# HM2102NLT_Transformer_Breakout_Board.net
KiCad netlist of a schematic drawn in EAGLE
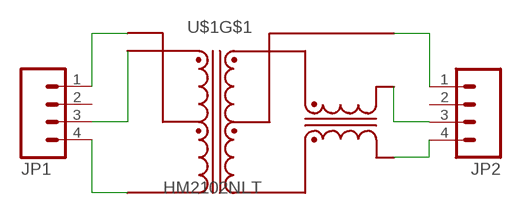
[diagram p0: schematic, sheet 1]

(export (version "E")
  (design (tool "Eeschema 10.0.6"))
  (components
    (comp (ref "JP1")
      (value "M04")
      (footprint "eagle-import:1X04")
      (libsource (lib "eagle-import") (part "M04"))
    )
    (comp (ref "JP2")
      (value "M04")
      (footprint "eagle-import:1X04")
      (libsource (lib "eagle-import") (part "M04"))
    )
    (comp (ref "U$1")
      (value "HM2102NLT")
      (footprint "eagle-import:HM2102NLT")
      (libsource (lib "eagle-import") (part "HM2102NLT"))
    )
  )
  (nets
    (net (code "1") (name "Net-(U$1A-MCT)") (class "Default")
      (node (ref "JP1") (pin "1") (pinfunction "1_1") (pintype "passive"))
      (node (ref "U$1") (pin "P$2") (pinfunction "MCT_P$2") (pintype "passive"))
    )
    (net (code "2") (name "Net-(U$1A-MX+)") (class "Default")
      (node (ref "JP1") (pin "3") (pinfunction "3_3") (pintype "passive"))
      (node (ref "U$1") (pin "P$1") (pinfunction "MX+_P$1") (pintype "passive"))
    )
    (net (code "3") (name "Net-(U$1A-MX-)") (class "Default")
      (node (ref "JP1") (pin "4") (pinfunction "4_4") (pintype "passive"))
      (node (ref "U$1") (pin "P$3") (pinfunction "MX-_P$3") (pintype "passive"))
    )
    (net (code "4") (name "Net-(U$1A-TCT)") (class "Default")
      (node (ref "JP2") (pin "1") (pinfunction "1_1") (pintype "passive"))
      (node (ref "U$1") (pin "P$11") (pinfunction "TCT_P$11") (pintype "passive"))
    )
    (net (code "5") (name "Net-(U$1A-TD+)") (class "Default")
      (node (ref "JP2") (pin "3") (pinfunction "3_3") (pintype "passive"))
      (node (ref "U$1") (pin "P$12") (pinfunction "TD+_P$12") (pintype "passive"))
    )
    (net (code "6") (name "Net-(U$1A-TD-)") (class "Default")
      (node (ref "JP2") (pin "4") (pinfunction "4_4") (pintype "passive"))
      (node (ref "U$1") (pin "P$10") (pinfunction "TD-_P$10") (pintype "passive"))
    )
    (net (code "7") (name "unconnected-(JP1-Pad2)") (class "Default")
      (node (ref "JP1") (pin "2") (pinfunction "2_2") (pintype "passive"))
    )
    (net (code "8") (name "unconnected-(JP2-Pad2)") (class "Default")
      (node (ref "JP2") (pin "2") (pinfunction "2_2") (pintype "passive"))
    )
  )
)
